# BrakeLight2024.net
KiCad netlist of a schematic drawn in Altium Designer
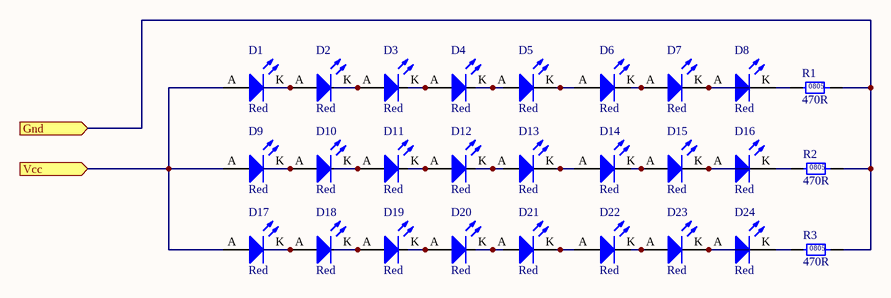
[diagram p0: BrakeLight2024.SchDoc]

(export (version "E")
  (design (tool "Eeschema 10.0.6"))
  (components
    (comp (ref "D1")
      (value "Red")
      (footprint "0805 LED")
      (description "Red LED Indication - Discrete 1.75V 0805 (2012 Metric)")
      (fields (field (name "PART NUMBER") "SML-210LTT86") (field (name "MANUFACTURER") "ROHM Semiconductor"))
      (libsource (lib "ts_standard_library") (part "LED"))
    )
    (comp (ref "D2")
      (value "Red")
      (footprint "0805 LED")
      (description "Red LED Indication - Discrete 1.75V 0805 (2012 Metric)")
      (fields (field (name "PART NUMBER") "SML-210LTT86") (field (name "MANUFACTURER") "ROHM Semiconductor"))
      (libsource (lib "ts_standard_library") (part "LED"))
    )
    (comp (ref "D3")
      (value "Red")
      (footprint "0805 LED")
      (description "Red LED Indication - Discrete 1.75V 0805 (2012 Metric)")
      (fields (field (name "PART NUMBER") "SML-210LTT86") (field (name "MANUFACTURER") "ROHM Semiconductor"))
      (libsource (lib "ts_standard_library") (part "LED"))
    )
    (comp (ref "D4")
      (value "Red")
      (footprint "0805 LED")
      (description "Red LED Indication - Discrete 1.75V 0805 (2012 Metric)")
      (fields (field (name "PART NUMBER") "SML-210LTT86") (field (name "MANUFACTURER") "ROHM Semiconductor"))
      (libsource (lib "ts_standard_library") (part "LED"))
    )
    (comp (ref "D5")
      (value "Red")
      (footprint "0805 LED")
      (description "Red LED Indication - Discrete 1.75V 0805 (2012 Metric)")
      (fields (field (name "PART NUMBER") "SML-210LTT86") (field (name "MANUFACTURER") "ROHM Semiconductor"))
      (libsource (lib "ts_standard_library") (part "LED"))
    )
    (comp (ref "D6")
      (value "Red")
      (footprint "0805 LED")
      (description "Red LED Indication - Discrete 1.75V 0805 (2012 Metric)")
      (fields (field (name "PART NUMBER") "SML-210LTT86") (field (name "MANUFACTURER") "ROHM Semiconductor"))
      (libsource (lib "ts_standard_library") (part "LED"))
    )
    (comp (ref "D7")
      (value "Red")
      (footprint "0805 LED")
      (description "Red LED Indication - Discrete 1.75V 0805 (2012 Metric)")
      (fields (field (name "PART NUMBER") "SML-210LTT86") (field (name "MANUFACTURER") "ROHM Semiconductor"))
      (libsource (lib "ts_standard_library") (part "LED"))
    )
    (comp (ref "D8")
      (value "Red")
      (footprint "0805 LED")
      (description "Red LED Indication - Discrete 1.75V 0805 (2012 Metric)")
      (fields (field (name "PART NUMBER") "SML-210LTT86") (field (name "MANUFACTURER") "ROHM Semiconductor"))
      (libsource (lib "ts_standard_library") (part "LED"))
    )
    (comp (ref "D9")
      (value "Red")
      (footprint "0805 LED")
      (description "Red LED Indication - Discrete 1.75V 0805 (2012 Metric)")
      (fields (field (name "PART NUMBER") "SML-210LTT86") (field (name "MANUFACTURER") "ROHM Semiconductor"))
      (libsource (lib "ts_standard_library") (part "LED"))
    )
    (comp (ref "D10")
      (value "Red")
      (footprint "0805 LED")
      (description "Red LED Indication - Discrete 1.75V 0805 (2012 Metric)")
      (fields (field (name "PART NUMBER") "SML-210LTT86") (field (name "MANUFACTURER") "ROHM Semiconductor"))
      (libsource (lib "ts_standard_library") (part "LED"))
    )
    (comp (ref "D11")
      (value "Red")
      (footprint "0805 LED")
      (description "Red LED Indication - Discrete 1.75V 0805 (2012 Metric)")
      (fields (field (name "PART NUMBER") "SML-210LTT86") (field (name "MANUFACTURER") "ROHM Semiconductor"))
      (libsource (lib "ts_standard_library") (part "LED"))
    )
    (comp (ref "D12")
      (value "Red")
      (footprint "0805 LED")
      (description "Red LED Indication - Discrete 1.75V 0805 (2012 Metric)")
      (fields (field (name "PART NUMBER") "SML-210LTT86") (field (name "MANUFACTURER") "ROHM Semiconductor"))
      (libsource (lib "ts_standard_library") (part "LED"))
    )
    (comp (ref "D13")
      (value "Red")
      (footprint "0805 LED")
      (description "Red LED Indication - Discrete 1.75V 0805 (2012 Metric)")
      (fields (field (name "PART NUMBER") "SML-210LTT86") (field (name "MANUFACTURER") "ROHM Semiconductor"))
      (libsource (lib "ts_standard_library") (part "LED"))
    )
    (comp (ref "D14")
      (value "Red")
      (footprint "0805 LED")
      (description "Red LED Indication - Discrete 1.75V 0805 (2012 Metric)")
      (fields (field (name "PART NUMBER") "SML-210LTT86") (field (name "MANUFACTURER") "ROHM Semiconductor"))
      (libsource (lib "ts_standard_library") (part "LED"))
    )
    (comp (ref "D15")
      (value "Red")
      (footprint "0805 LED")
      (description "Red LED Indication - Discrete 1.75V 0805 (2012 Metric)")
      (fields (field (name "PART NUMBER") "SML-210LTT86") (field (name "MANUFACTURER") "ROHM Semiconductor"))
      (libsource (lib "ts_standard_library") (part "LED"))
    )
    (comp (ref "D16")
      (value "Red")
      (footprint "0805 LED")
      (description "Red LED Indication - Discrete 1.75V 0805 (2012 Metric)")
      (fields (field (name "PART NUMBER") "SML-210LTT86") (field (name "MANUFACTURER") "ROHM Semiconductor"))
      (libsource (lib "ts_standard_library") (part "LED"))
    )
    (comp (ref "D17")
      (value "Red")
      (footprint "0805 LED")
      (description "Red LED Indication - Discrete 1.75V 0805 (2012 Metric)")
      (fields (field (name "PART NUMBER") "SML-210LTT86") (field (name "MANUFACTURER") "ROHM Semiconductor"))
      (libsource (lib "ts_standard_library") (part "LED"))
    )
    (comp (ref "D18")
      (value "Red")
      (footprint "0805 LED")
      (description "Red LED Indication - Discrete 1.75V 0805 (2012 Metric)")
      (fields (field (name "PART NUMBER") "SML-210LTT86") (field (name "MANUFACTURER") "ROHM Semiconductor"))
      (libsource (lib "ts_standard_library") (part "LED"))
    )
    (comp (ref "D19")
      (value "Red")
      (footprint "0805 LED")
      (description "Red LED Indication - Discrete 1.75V 0805 (2012 Metric)")
      (fields (field (name "PART NUMBER") "SML-210LTT86") (field (name "MANUFACTURER") "ROHM Semiconductor"))
      (libsource (lib "ts_standard_library") (part "LED"))
    )
    (comp (ref "D20")
      (value "Red")
      (footprint "0805 LED")
      (description "Red LED Indication - Discrete 1.75V 0805 (2012 Metric)")
      (fields (field (name "PART NUMBER") "SML-210LTT86") (field (name "MANUFACTURER") "ROHM Semiconductor"))
      (libsource (lib "ts_standard_library") (part "LED"))
    )
    (comp (ref "D21")
      (value "Red")
      (footprint "0805 LED")
      (description "Red LED Indication - Discrete 1.75V 0805 (2012 Metric)")
      (fields (field (name "PART NUMBER") "SML-210LTT86") (field (name "MANUFACTURER") "ROHM Semiconductor"))
      (libsource (lib "ts_standard_library") (part "LED"))
    )
    (comp (ref "D22")
      (value "Red")
      (footprint "0805 LED")
      (description "Red LED Indication - Discrete 1.75V 0805 (2012 Metric)")
      (fields (field (name "PART NUMBER") "SML-210LTT86") (field (name "MANUFACTURER") "ROHM Semiconductor"))
      (libsource (lib "ts_standard_library") (part "LED"))
    )
    (comp (ref "D23")
      (value "Red")
      (footprint "0805 LED")
      (description "Red LED Indication - Discrete 1.75V 0805 (2012 Metric)")
      (fields (field (name "PART NUMBER") "SML-210LTT86") (field (name "MANUFACTURER") "ROHM Semiconductor"))
      (libsource (lib "ts_standard_library") (part "LED"))
    )
    (comp (ref "D24")
      (value "Red")
      (footprint "0805 LED")
      (description "Red LED Indication - Discrete 1.75V 0805 (2012 Metric)")
      (fields (field (name "PART NUMBER") "SML-210LTT86") (field (name "MANUFACTURER") "ROHM Semiconductor"))
      (libsource (lib "ts_standard_library") (part "LED"))
    )
    (comp (ref "R1")
      (value "470R")
      (footprint "0805")
      (fields
        (field (name "PART NUMBER") "RC0805FR07470RL")
        (field (name "MANUFACTURER") "YAGEO")
        (field (name "TOLERANCE") "0.01")
      )
      (libsource (lib "ts_standard_library") (part "Resistor 0805"))
    )
    (comp (ref "R2")
      (value "470R")
      (footprint "0805")
      (fields
        (field (name "PART NUMBER") "RC0805FR07470RL")
        (field (name "MANUFACTURER") "YAGEO")
        (field (name "TOLERANCE") "0.01")
      )
      (libsource (lib "ts_standard_library") (part "Resistor 0805"))
    )
    (comp (ref "R3")
      (value "470R")
      (footprint "0805")
      (fields
        (field (name "PART NUMBER") "RC0805FR07470RL")
        (field (name "MANUFACTURER") "YAGEO")
        (field (name "TOLERANCE") "0.01")
      )
      (libsource (lib "ts_standard_library") (part "Resistor 0805"))
    )
  )
  (nets
    (net (code "1") (name "/Gnd") (class "Default")
      (node (ref "R1") (pin "2") (pinfunction "2_2") (pintype "passive"))
      (node (ref "R2") (pin "2") (pinfunction "2_2") (pintype "passive"))
      (node (ref "R3") (pin "2") (pinfunction "2_2") (pintype "passive"))
    )
    (net (code "2") (name "/Vcc") (class "Default")
      (node (ref "D1") (pin "A") (pinfunction "A_A") (pintype "passive"))
      (node (ref "D17") (pin "A") (pinfunction "A_A") (pintype "passive"))
      (node (ref "D9") (pin "A") (pinfunction "A_A") (pintype "passive"))
    )
    (net (code "3") (name "Net-(D1-PadK)") (class "Default")
      (node (ref "D1") (pin "K") (pinfunction "K_K") (pintype "passive"))
      (node (ref "D2") (pin "A") (pinfunction "A_A") (pintype "passive"))
    )
    (net (code "4") (name "Net-(D2-PadK)") (class "Default")
      (node (ref "D2") (pin "K") (pinfunction "K_K") (pintype "passive"))
      (node (ref "D3") (pin "A") (pinfunction "A_A") (pintype "passive"))
    )
    (net (code "5") (name "Net-(D3-PadK)") (class "Default")
      (node (ref "D3") (pin "K") (pinfunction "K_K") (pintype "passive"))
      (node (ref "D4") (pin "A") (pinfunction "A_A") (pintype "passive"))
    )
    (net (code "6") (name "Net-(D4-PadK)") (class "Default")
      (node (ref "D4") (pin "K") (pinfunction "K_K") (pintype "passive"))
      (node (ref "D5") (pin "A") (pinfunction "A_A") (pintype "passive"))
    )
    (net (code "7") (name "Net-(D5-PadK)") (class "Default")
      (node (ref "D5") (pin "K") (pinfunction "K_K") (pintype "passive"))
      (node (ref "D6") (pin "A") (pinfunction "A_A") (pintype "passive"))
    )
    (net (code "8") (name "Net-(D6-PadK)") (class "Default")
      (node (ref "D6") (pin "K") (pinfunction "K_K") (pintype "passive"))
      (node (ref "D7") (pin "A") (pinfunction "A_A") (pintype "passive"))
    )
    (net (code "9") (name "Net-(D7-PadK)") (class "Default")
      (node (ref "D7") (pin "K") (pinfunction "K_K") (pintype "passive"))
      (node (ref "D8") (pin "A") (pinfunction "A_A") (pintype "passive"))
    )
    (net (code "10") (name "Net-(D8-PadK)") (class "Default")
      (node (ref "D8") (pin "K") (pinfunction "K_K") (pintype "passive"))
      (node (ref "R1") (pin "1") (pinfunction "1_1") (pintype "passive"))
    )
    (net (code "11") (name "Net-(D10-PadA)") (class "Default")
      (node (ref "D10") (pin "A") (pinfunction "A_A") (pintype "passive"))
      (node (ref "D9") (pin "K") (pinfunction "K_K") (pintype "passive"))
    )
    (net (code "12") (name "Net-(D10-PadK)") (class "Default")
      (node (ref "D10") (pin "K") (pinfunction "K_K") (pintype "passive"))
      (node (ref "D11") (pin "A") (pinfunction "A_A") (pintype "passive"))
    )
    (net (code "13") (name "Net-(D11-PadK)") (class "Default")
      (node (ref "D11") (pin "K") (pinfunction "K_K") (pintype "passive"))
      (node (ref "D12") (pin "A") (pinfunction "A_A") (pintype "passive"))
    )
    (net (code "14") (name "Net-(D12-PadK)") (class "Default")
      (node (ref "D12") (pin "K") (pinfunction "K_K") (pintype "passive"))
      (node (ref "D13") (pin "A") (pinfunction "A_A") (pintype "passive"))
    )
    (net (code "15") (name "Net-(D13-PadK)") (class "Default")
      (node (ref "D13") (pin "K") (pinfunction "K_K") (pintype "passive"))
      (node (ref "D14") (pin "A") (pinfunction "A_A") (pintype "passive"))
    )
    (net (code "16") (name "Net-(D14-PadK)") (class "Default")
      (node (ref "D14") (pin "K") (pinfunction "K_K") (pintype "passive"))
      (node (ref "D15") (pin "A") (pinfunction "A_A") (pintype "passive"))
    )
    (net (code "17") (name "Net-(D15-PadK)") (class "Default")
      (node (ref "D15") (pin "K") (pinfunction "K_K") (pintype "passive"))
      (node (ref "D16") (pin "A") (pinfunction "A_A") (pintype "passive"))
    )
    (net (code "18") (name "Net-(D16-PadK)") (class "Default")
      (node (ref "D16") (pin "K") (pinfunction "K_K") (pintype "passive"))
      (node (ref "R2") (pin "1") (pinfunction "1_1") (pintype "passive"))
    )
    (net (code "19") (name "Net-(D17-PadK)") (class "Default")
      (node (ref "D17") (pin "K") (pinfunction "K_K") (pintype "passive"))
      (node (ref "D18") (pin "A") (pinfunction "A_A") (pintype "passive"))
    )
    (net (code "20") (name "Net-(D18-PadK)") (class "Default")
      (node (ref "D18") (pin "K") (pinfunction "K_K") (pintype "passive"))
      (node (ref "D19") (pin "A") (pinfunction "A_A") (pintype "passive"))
    )
    (net (code "21") (name "Net-(D19-PadK)") (class "Default")
      (node (ref "D19") (pin "K") (pinfunction "K_K") (pintype "passive"))
      (node (ref "D20") (pin "A") (pinfunction "A_A") (pintype "passive"))
    )
    (net (code "22") (name "Net-(D20-PadK)") (class "Default")
      (node (ref "D20") (pin "K") (pinfunction "K_K") (pintype "passive"))
      (node (ref "D21") (pin "A") (pinfunction "A_A") (pintype "passive"))
    )
    (net (code "23") (name "Net-(D21-PadK)") (class "Default")
      (node (ref "D21") (pin "K") (pinfunction "K_K") (pintype "passive"))
      (node (ref "D22") (pin "A") (pinfunction "A_A") (pintype "passive"))
    )
    (net (code "24") (name "Net-(D22-PadK)") (class "Default")
      (node (ref "D22") (pin "K") (pinfunction "K_K") (pintype "passive"))
      (node (ref "D23") (pin "A") (pinfunction "A_A") (pintype "passive"))
    )
    (net (code "25") (name "Net-(D23-PadK)") (class "Default")
      (node (ref "D23") (pin "K") (pinfunction "K_K") (pintype "passive"))
      (node (ref "D24") (pin "A") (pinfunction "A_A") (pintype "passive"))
    )
    (net (code "26") (name "Net-(D24-PadK)") (class "Default")
      (node (ref "D24") (pin "K") (pinfunction "K_K") (pintype "passive"))
      (node (ref "R3") (pin "1") (pinfunction "1_1") (pintype "passive"))
    )
  )
)
